# MPS_Drive_Amp_2.net
KiCad netlist of a schematic drawn in EAGLE
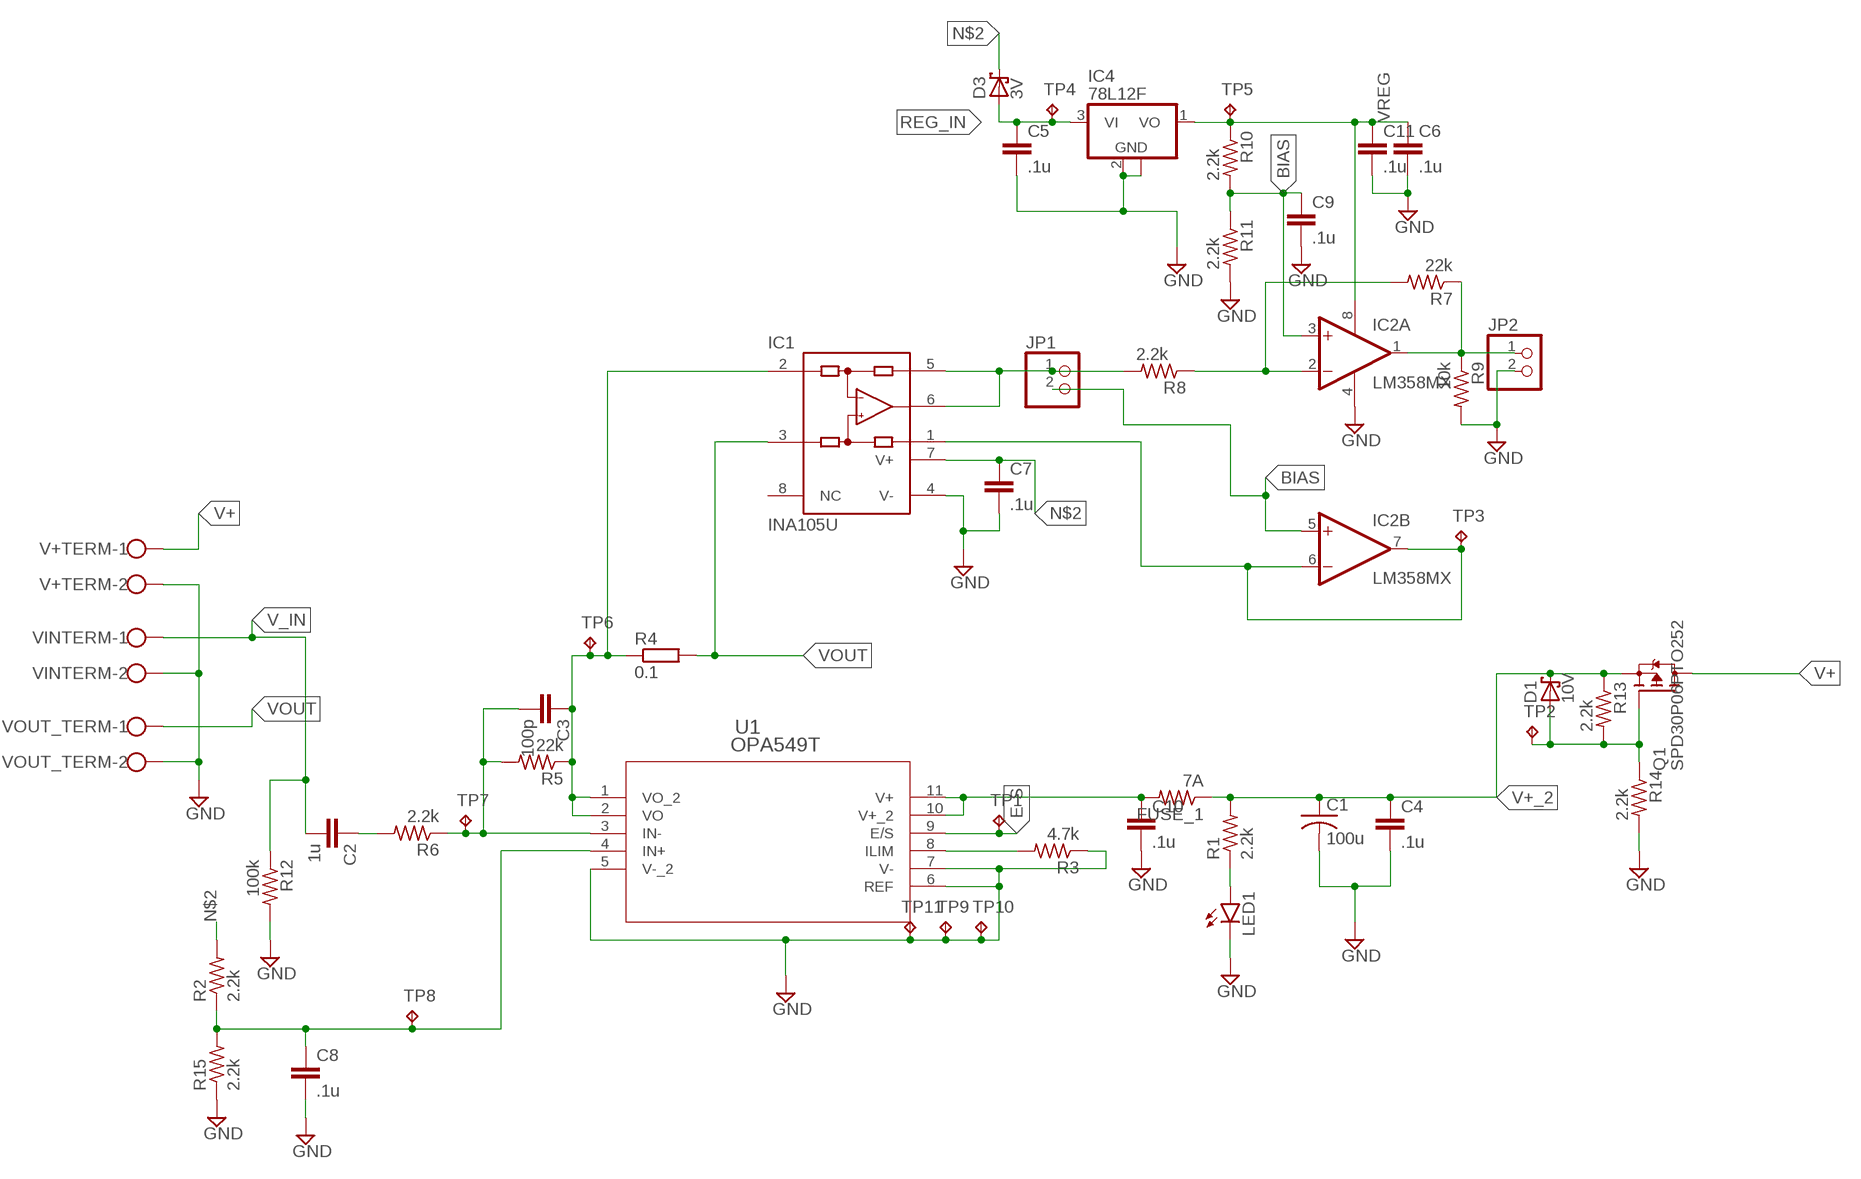
[diagram p0: schematic, sheet 1]

(export (version "E")
  (design (tool "Eeschema 10.0.6"))
  (components
    (comp (ref "C1")
      (value "100u")
      (footprint "eagle-import:C050-025X075")
      (libsource (lib "eagle-import") (part "C-US050-025X075"))
    )
    (comp (ref "C2")
      (value "1u")
      (footprint "eagle-import:C1206")
      (libsource (lib "eagle-import") (part "C-EUC1206"))
    )
    (comp (ref "C3")
      (value "100p")
      (footprint "eagle-import:C1206")
      (libsource (lib "eagle-import") (part "C-EUC1206"))
    )
    (comp (ref "C4")
      (value ".1u")
      (footprint "eagle-import:C1206")
      (libsource (lib "eagle-import") (part "C-EUC1206"))
    )
    (comp (ref "C5")
      (value ".1u")
      (footprint "eagle-import:C1206")
      (libsource (lib "eagle-import") (part "C-EUC1206"))
    )
    (comp (ref "C6")
      (value ".1u")
      (footprint "eagle-import:C1206")
      (libsource (lib "eagle-import") (part "C-EUC1206"))
    )
    (comp (ref "C7")
      (value ".1u")
      (footprint "eagle-import:C1206")
      (libsource (lib "eagle-import") (part "C-EUC1206"))
    )
    (comp (ref "C8")
      (value ".1u")
      (footprint "eagle-import:C1206")
      (libsource (lib "eagle-import") (part "C-EUC1206"))
    )
    (comp (ref "C9")
      (value ".1u")
      (footprint "eagle-import:C1206")
      (libsource (lib "eagle-import") (part "C-EUC1206"))
    )
    (comp (ref "C10")
      (value ".1u")
      (footprint "eagle-import:C1206")
      (libsource (lib "eagle-import") (part "C-EUC1206"))
    )
    (comp (ref "C11")
      (value ".1u")
      (footprint "eagle-import:C1206")
      (libsource (lib "eagle-import") (part "C-EUC1206"))
    )
    (comp (ref "D1")
      (value "10V")
      (footprint "eagle-import:DO35-7")
      (libsource (lib "eagle-import") (part "SCHOTTKY-DIODEDO35-7"))
    )
    (comp (ref "D3")
      (value "3V")
      (footprint "eagle-import:DO35-7")
      (libsource (lib "eagle-import") (part "SCHOTTKY-DIODEDO35-7"))
    )
    (comp (ref "FUSE_1")
      (value "7A")
      (footprint "eagle-import:R1206")
      (libsource (lib "eagle-import") (part "R-US_R1206"))
    )
    (comp (ref "IC1")
      (value "INA105U")
      (footprint "eagle-import:SO08")
      (fields (field (name "MF") "TEXAS INSTRUMENTS") (field (name "MPN") "INA105KU"))
      (libsource (lib "eagle-import") (part "INA105U"))
    )
    (comp (ref "IC2")
      (value "LM358MX")
      (footprint "eagle-import:SO08")
      (libsource (lib "eagle-import") (part "LM358MX"))
    )
    (comp (ref "IC4")
      (value "78L12F")
      (footprint "eagle-import:SOT89")
      (libsource (lib "eagle-import") (part "78LF12"))
    )
    (comp (ref "JP1")
      (value "PINHD-1X2")
      (footprint "eagle-import:1X02")
      (libsource (lib "eagle-import") (part "PINHD-1X2"))
    )
    (comp (ref "JP2")
      (value "PINHD-1X2")
      (footprint "eagle-import:1X02")
      (libsource (lib "eagle-import") (part "PINHD-1X2"))
    )
    (comp (ref "LED1")
      (value "LEDCHIPLED_0805")
      (footprint "eagle-import:CHIPLED_0805")
      (libsource (lib "eagle-import") (part "LEDCHIPLED_0805"))
    )
    (comp (ref "Q1")
      (value "SPD30P06PTO252")
      (footprint "eagle-import:TO252")
      (libsource (lib "eagle-import") (part "SPD30P06PTO252"))
    )
    (comp (ref "R1")
      (value "2.2k")
      (footprint "eagle-import:R1206")
      (libsource (lib "eagle-import") (part "R-US_R1206"))
    )
    (comp (ref "R2")
      (value "2.2k")
      (footprint "eagle-import:R1206")
      (libsource (lib "eagle-import") (part "R-US_R1206"))
    )
    (comp (ref "R3")
      (value "4.7k")
      (footprint "eagle-import:R1206")
      (libsource (lib "eagle-import") (part "R-US_R1206"))
    )
    (comp (ref "R4")
      (value "0.1")
      (footprint "eagle-import:VTA52")
      (libsource (lib "eagle-import") (part "R-EU_VTA52"))
    )
    (comp (ref "R5")
      (value "22k")
      (footprint "eagle-import:R1206")
      (libsource (lib "eagle-import") (part "R-US_R1206"))
    )
    (comp (ref "R6")
      (value "2.2k")
      (footprint "eagle-import:R1206")
      (libsource (lib "eagle-import") (part "R-US_R1206"))
    )
    (comp (ref "R7")
      (value "22k")
      (footprint "eagle-import:R1206")
      (libsource (lib "eagle-import") (part "R-US_R1206"))
    )
    (comp (ref "R8")
      (value "2.2k")
      (footprint "eagle-import:R1206")
      (libsource (lib "eagle-import") (part "R-US_R1206"))
    )
    (comp (ref "R9")
      (value "10k")
      (footprint "eagle-import:R1206")
      (libsource (lib "eagle-import") (part "R-US_R1206"))
    )
    (comp (ref "R10")
      (value "2.2k")
      (footprint "eagle-import:R1206")
      (libsource (lib "eagle-import") (part "R-US_R1206"))
    )
    (comp (ref "R11")
      (value "2.2k")
      (footprint "eagle-import:R1206")
      (libsource (lib "eagle-import") (part "R-US_R1206"))
    )
    (comp (ref "R12")
      (value "100k")
      (footprint "eagle-import:R1206")
      (libsource (lib "eagle-import") (part "R-US_R1206"))
    )
    (comp (ref "R13")
      (value "2.2k")
      (footprint "eagle-import:R1206")
      (libsource (lib "eagle-import") (part "R-US_R1206"))
    )
    (comp (ref "R14")
      (value "2.2k")
      (footprint "eagle-import:R1206")
      (libsource (lib "eagle-import") (part "R-US_R1206"))
    )
    (comp (ref "R15")
      (value "2.2k")
      (footprint "eagle-import:R1206")
      (libsource (lib "eagle-import") (part "R-US_R1206"))
    )
    (comp (ref "TP1")
      (value "TPTP20SQ")
      (footprint "eagle-import:TP20SQ")
      (libsource (lib "eagle-import") (part "TPTP20SQ"))
    )
    (comp (ref "TP2")
      (value "TPTP20SQ")
      (footprint "eagle-import:TP20SQ")
      (libsource (lib "eagle-import") (part "TPTP20SQ"))
    )
    (comp (ref "TP3")
      (value "TPTP20SQ")
      (footprint "eagle-import:TP20SQ")
      (libsource (lib "eagle-import") (part "TPTP20SQ"))
    )
    (comp (ref "TP4")
      (value "TPTP20SQ")
      (footprint "eagle-import:TP20SQ")
      (libsource (lib "eagle-import") (part "TPTP20SQ"))
    )
    (comp (ref "TP5")
      (value "TPTP20SQ")
      (footprint "eagle-import:TP20SQ")
      (libsource (lib "eagle-import") (part "TPTP20SQ"))
    )
    (comp (ref "TP6")
      (value "TPTP20SQ")
      (footprint "eagle-import:TP20SQ")
      (libsource (lib "eagle-import") (part "TPTP20SQ"))
    )
    (comp (ref "TP7")
      (value "TPTP20SQ")
      (footprint "eagle-import:TP20SQ")
      (libsource (lib "eagle-import") (part "TPTP20SQ"))
    )
    (comp (ref "TP8")
      (value "TPTP20SQ")
      (footprint "eagle-import:TP20SQ")
      (libsource (lib "eagle-import") (part "TPTP20SQ"))
    )
    (comp (ref "TP9")
      (value "TPTP20SQ")
      (footprint "eagle-import:TP20SQ")
      (libsource (lib "eagle-import") (part "TPTP20SQ"))
    )
    (comp (ref "TP10")
      (value "TPTP20SQ")
      (footprint "eagle-import:TP20SQ")
      (libsource (lib "eagle-import") (part "TPTP20SQ"))
    )
    (comp (ref "TP11")
      (value "TPTP20SQ")
      (footprint "eagle-import:TP20SQ")
      (libsource (lib "eagle-import") (part "TPTP20SQ"))
    )
    (comp (ref "U1")
      (value "OPA549T")
      (footprint "eagle-import:KV11")
      (fields (field (name "GENERIC_PART_NUMBER") "OPA549") (field (name "MANUFACTURER") "Texas Instruments"))
      (libsource (lib "eagle-import") (part "OPA549T"))
    )
    (comp (ref "V+TERM")
      (value "W237-102")
      (footprint "eagle-import:W237-102")
      (fields (field (name "MPN") "237-102"))
      (libsource (lib "eagle-import") (part "W237-102"))
    )
    (comp (ref "VINTERM")
      (value "W237-102")
      (footprint "eagle-import:W237-102")
      (fields (field (name "MPN") "237-102"))
      (libsource (lib "eagle-import") (part "W237-102"))
    )
    (comp (ref "VOUT_TERM")
      (value "W237-102")
      (footprint "eagle-import:W237-102")
      (fields (field (name "MPN") "237-102"))
      (libsource (lib "eagle-import") (part "W237-102"))
    )
  )
  (nets
    (net (code "1") (name "/VREG") (class "Default")
      (node (ref "C11") (pin "1") (pinfunction "1_1") (pintype "passive"))
      (node (ref "C6") (pin "1") (pinfunction "1_1") (pintype "passive"))
      (node (ref "IC2") (pin "8") (pinfunction "V+_8") (pintype "power_in"))
      (node (ref "IC4") (pin "1") (pinfunction "VO_1") (pintype "passive"))
      (node (ref "R10") (pin "1") (pinfunction "1_1") (pintype "passive"))
      (node (ref "TP5") (pin "TP") (pinfunction "TP_TP") (pintype "input"))
    )
    (net (code "2") (name "BIAS") (class "Default")
      (node (ref "C9") (pin "1") (pinfunction "1_1") (pintype "passive"))
      (node (ref "IC2") (pin "3") (pinfunction "+IN_3") (pintype "input"))
      (node (ref "IC2") (pin "5") (pinfunction "+IN_5") (pintype "input"))
      (node (ref "JP1") (pin "2") (pinfunction "2_2") (pintype "passive"))
      (node (ref "R10") (pin "2") (pinfunction "2_2") (pintype "passive"))
      (node (ref "R11") (pin "1") (pinfunction "1_1") (pintype "passive"))
    )
    (net (code "3") (name "E-S") (class "Default")
      (node (ref "TP1") (pin "TP") (pinfunction "TP_TP") (pintype "input"))
      (node (ref "U1") (pin "9") (pinfunction "E/S_9") (pintype "passive"))
    )
    (net (code "4") (name "GND") (class "Default")
      (node (ref "C1") (pin "2") (pinfunction "2_2") (pintype "passive"))
      (node (ref "C10") (pin "2") (pinfunction "2_2") (pintype "passive"))
      (node (ref "C11") (pin "2") (pinfunction "2_2") (pintype "passive"))
      (node (ref "C4") (pin "2") (pinfunction "2_2") (pintype "passive"))
      (node (ref "C5") (pin "2") (pinfunction "2_2") (pintype "passive"))
      (node (ref "C6") (pin "2") (pinfunction "2_2") (pintype "passive"))
      (node (ref "C7") (pin "2") (pinfunction "2_2") (pintype "passive"))
      (node (ref "C8") (pin "2") (pinfunction "2_2") (pintype "passive"))
      (node (ref "C9") (pin "2") (pinfunction "2_2") (pintype "passive"))
      (node (ref "IC1") (pin "4") (pinfunction "V-_4") (pintype "power_in"))
      (node (ref "IC2") (pin "4") (pinfunction "V-_4") (pintype "power_in"))
      (node (ref "IC4") (pin "2") (pinfunction "GND_2") (pintype "passive"))
      (node (ref "IC4") (pin "2@1") (pinfunction "GND_2@1") (pintype "passive"))
      (node (ref "JP2") (pin "2") (pinfunction "2_2") (pintype "passive"))
      (node (ref "LED1") (pin "C") (pinfunction "C_C") (pintype "passive"))
      (node (ref "R11") (pin "2") (pinfunction "2_2") (pintype "passive"))
      (node (ref "R12") (pin "2") (pinfunction "2_2") (pintype "passive"))
      (node (ref "R14") (pin "2") (pinfunction "2_2") (pintype "passive"))
      (node (ref "R15") (pin "1") (pinfunction "1_1") (pintype "passive"))
      (node (ref "R3") (pin "1") (pinfunction "1_1") (pintype "passive"))
      (node (ref "R9") (pin "2") (pinfunction "2_2") (pintype "passive"))
      (node (ref "TP10") (pin "TP") (pinfunction "TP_TP") (pintype "input"))
      (node (ref "TP11") (pin "TP") (pinfunction "TP_TP") (pintype "input"))
      (node (ref "TP9") (pin "TP") (pinfunction "TP_TP") (pintype "input"))
      (node (ref "U1") (pin "5") (pinfunction "V-_2_5") (pintype "power_in"))
      (node (ref "U1") (pin "6") (pinfunction "REF_6") (pintype "power_in"))
      (node (ref "U1") (pin "7") (pinfunction "V-_7") (pintype "power_in"))
      (node (ref "V+TERM") (pin "2") (pinfunction "KL_2") (pintype "passive"))
      (node (ref "VINTERM") (pin "2") (pinfunction "KL_2") (pintype "passive"))
      (node (ref "VOUT_TERM") (pin "2") (pinfunction "KL_2") (pintype "passive"))
    )
    (net (code "5") (name "N$2") (class "Default")
      (node (ref "C10") (pin "1") (pinfunction "1_1") (pintype "passive"))
      (node (ref "C7") (pin "1") (pinfunction "1_1") (pintype "passive"))
      (node (ref "D3") (pin "C") (pinfunction "C_C") (pintype "passive"))
      (node (ref "FUSE_1") (pin "2") (pinfunction "2_2") (pintype "passive"))
      (node (ref "IC1") (pin "7") (pinfunction "V+_7") (pintype "power_in"))
      (node (ref "R2") (pin "2") (pinfunction "2_2") (pintype "passive"))
      (node (ref "U1") (pin "10") (pinfunction "V+_2_10") (pintype "power_in"))
      (node (ref "U1") (pin "11") (pinfunction "V+_11") (pintype "power_in"))
    )
    (net (code "6") (name "Net-(C2-Pad1)") (class "Default")
      (node (ref "C2") (pin "1") (pinfunction "1_1") (pintype "passive"))
      (node (ref "R6") (pin "2") (pinfunction "2_2") (pintype "passive"))
    )
    (net (code "7") (name "Net-(IC1--IN)") (class "Default")
      (node (ref "C3") (pin "1") (pinfunction "1_1") (pintype "passive"))
      (node (ref "IC1") (pin "2") (pinfunction "-IN_2") (pintype "input"))
      (node (ref "R4") (pin "1") (pinfunction "1_1") (pintype "passive"))
      (node (ref "R5") (pin "1") (pinfunction "1_1") (pintype "passive"))
      (node (ref "TP6") (pin "TP") (pinfunction "TP_TP") (pintype "input"))
      (node (ref "U1") (pin "1") (pinfunction "VO_2_1") (pintype "output"))
      (node (ref "U1") (pin "2") (pinfunction "VO_2") (pintype "output"))
    )
    (net (code "8") (name "Net-(IC1-OUT)") (class "Default")
      (node (ref "IC1") (pin "5") (pinfunction "SENSE_5") (pintype "passive"))
      (node (ref "IC1") (pin "6") (pinfunction "OUT_6") (pintype "output"))
      (node (ref "JP1") (pin "1") (pinfunction "1_1") (pintype "passive"))
      (node (ref "R8") (pin "2") (pinfunction "2_2") (pintype "passive"))
    )
    (net (code "9") (name "Net-(IC1-REF)") (class "Default")
      (node (ref "IC1") (pin "1") (pinfunction "REF_1") (pintype "passive"))
      (node (ref "IC2") (pin "6") (pinfunction "-IN_6") (pintype "input"))
      (node (ref "IC2") (pin "7") (pinfunction "OUT_7") (pintype "output"))
      (node (ref "TP3") (pin "TP") (pinfunction "TP_TP") (pintype "input"))
    )
    (net (code "10") (name "Net-(IC2A--IN)") (class "Default")
      (node (ref "IC2") (pin "2") (pinfunction "-IN_2") (pintype "input"))
      (node (ref "R7") (pin "2") (pinfunction "2_2") (pintype "passive"))
      (node (ref "R8") (pin "1") (pinfunction "1_1") (pintype "passive"))
    )
    (net (code "11") (name "Net-(IC2A-OUT)") (class "Default")
      (node (ref "IC2") (pin "1") (pinfunction "OUT_1") (pintype "output"))
      (node (ref "JP2") (pin "1") (pinfunction "1_1") (pintype "passive"))
      (node (ref "R7") (pin "1") (pinfunction "1_1") (pintype "passive"))
      (node (ref "R9") (pin "1") (pinfunction "1_1") (pintype "passive"))
    )
    (net (code "12") (name "Net-(LED1-PadA)") (class "Default")
      (node (ref "LED1") (pin "A") (pinfunction "A_A") (pintype "passive"))
      (node (ref "R1") (pin "1") (pinfunction "1_1") (pintype "passive"))
    )
    (net (code "13") (name "Net-(Q1-G)") (class "Default")
      (node (ref "D1") (pin "A") (pinfunction "A_A") (pintype "passive"))
      (node (ref "Q1") (pin "1") (pinfunction "G_1") (pintype "passive"))
      (node (ref "R13") (pin "2") (pinfunction "2_2") (pintype "passive"))
      (node (ref "R14") (pin "1") (pinfunction "1_1") (pintype "passive"))
      (node (ref "TP2") (pin "TP") (pinfunction "TP_TP") (pintype "input"))
    )
    (net (code "14") (name "Net-(U1-ILIM)") (class "Default")
      (node (ref "R3") (pin "2") (pinfunction "2_2") (pintype "passive"))
      (node (ref "U1") (pin "8") (pinfunction "ILIM_8") (pintype "passive"))
    )
    (net (code "15") (name "Net-(U1-IN+)") (class "Default")
      (node (ref "C8") (pin "1") (pinfunction "1_1") (pintype "passive"))
      (node (ref "R15") (pin "2") (pinfunction "2_2") (pintype "passive"))
      (node (ref "R2") (pin "1") (pinfunction "1_1") (pintype "passive"))
      (node (ref "TP8") (pin "TP") (pinfunction "TP_TP") (pintype "input"))
      (node (ref "U1") (pin "4") (pinfunction "IN+_4") (pintype "input"))
    )
    (net (code "16") (name "Net-(U1-IN-)") (class "Default")
      (node (ref "C3") (pin "2") (pinfunction "2_2") (pintype "passive"))
      (node (ref "R5") (pin "2") (pinfunction "2_2") (pintype "passive"))
      (node (ref "R6") (pin "1") (pinfunction "1_1") (pintype "passive"))
      (node (ref "TP7") (pin "TP") (pinfunction "TP_TP") (pintype "input"))
      (node (ref "U1") (pin "3") (pinfunction "IN-_3") (pintype "input"))
    )
    (net (code "17") (name "REG_IN") (class "Default")
      (node (ref "C5") (pin "1") (pinfunction "1_1") (pintype "passive"))
      (node (ref "D3") (pin "A") (pinfunction "A_A") (pintype "passive"))
      (node (ref "IC4") (pin "3") (pinfunction "VI_3") (pintype "input"))
      (node (ref "TP4") (pin "TP") (pinfunction "TP_TP") (pintype "input"))
    )
    (net (code "18") (name "V+") (class "Default")
      (node (ref "Q1") (pin "3") (pinfunction "D_3") (pintype "passive"))
      (node (ref "V+TERM") (pin "1") (pinfunction "KL_1") (pintype "passive"))
    )
    (net (code "19") (name "V+_2") (class "Default")
      (node (ref "C1") (pin "1") (pinfunction "1_1") (pintype "passive"))
      (node (ref "C4") (pin "1") (pinfunction "1_1") (pintype "passive"))
      (node (ref "D1") (pin "C") (pinfunction "C_C") (pintype "passive"))
      (node (ref "FUSE_1") (pin "1") (pinfunction "1_1") (pintype "passive"))
      (node (ref "Q1") (pin "2") (pinfunction "S_2") (pintype "passive"))
      (node (ref "R1") (pin "2") (pinfunction "2_2") (pintype "passive"))
      (node (ref "R13") (pin "1") (pinfunction "1_1") (pintype "passive"))
    )
    (net (code "20") (name "VOUT") (class "Default")
      (node (ref "IC1") (pin "3") (pinfunction "+IN_3") (pintype "input"))
      (node (ref "R4") (pin "2") (pinfunction "2_2") (pintype "passive"))
      (node (ref "VOUT_TERM") (pin "1") (pinfunction "KL_1") (pintype "passive"))
    )
    (net (code "21") (name "V_IN") (class "Default")
      (node (ref "C2") (pin "2") (pinfunction "2_2") (pintype "passive"))
      (node (ref "R12") (pin "1") (pinfunction "1_1") (pintype "passive"))
      (node (ref "VINTERM") (pin "1") (pinfunction "KL_1") (pintype "passive"))
    )
    (net (code "22") (name "unconnected-(IC1-NC-Pad8)") (class "Default")
      (node (ref "IC1") (pin "8") (pinfunction "NC_8") (pintype "no_connect"))
    )
  )
)
